# 1-Schematic_USB-C_Serial.net
KiCad netlist of a schematic drawn in EasyEDA
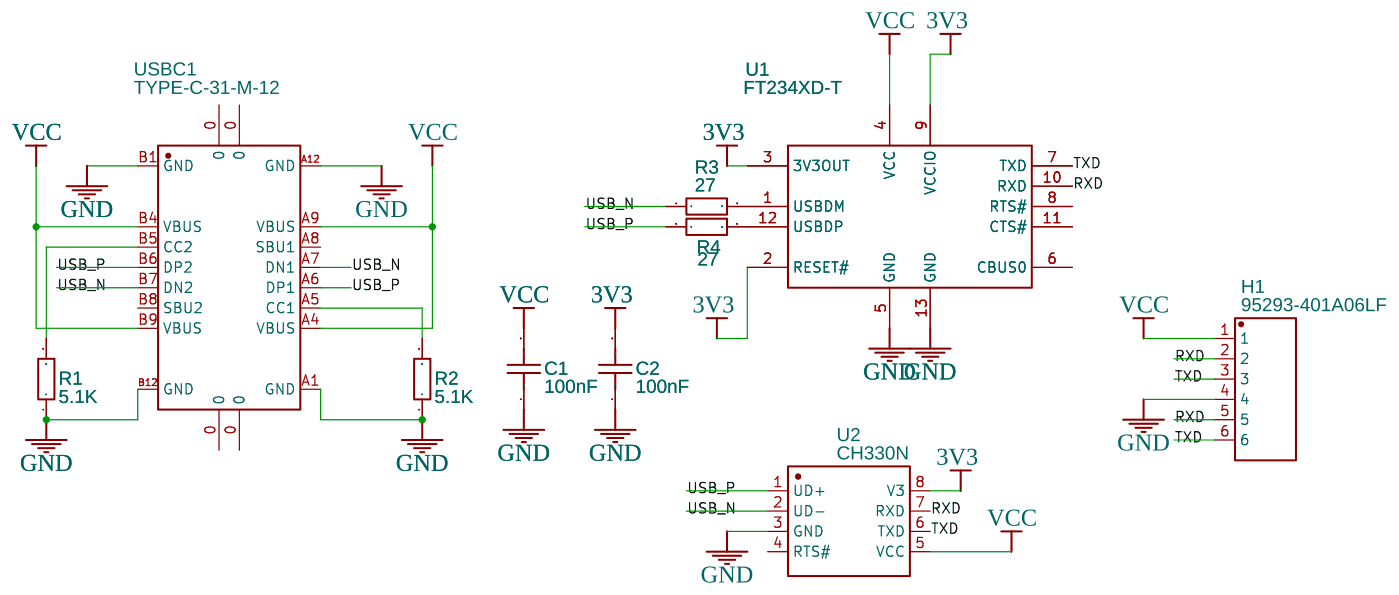
[diagram p0: schematic sheet]

(export (version "E")
  (design (tool "Eeschema 10.0.6"))
  (components
    (comp (ref "C1")
      (value "100nF")
      (fields
        (field (name "BOM_Manufacturer Part") "CC0603KRX7R9BB104")
        (field (name "BOM_Supplier Part") "C14663")
      )
      (libsource (lib "") (part "CC0603KRX7R9BB104"))
    )
    (comp (ref "C2")
      (value "100nF")
      (fields
        (field (name "BOM_Manufacturer Part") "CC0603KRX7R9BB104")
        (field (name "BOM_Supplier Part") "C14663")
      )
      (libsource (lib "") (part "CC0603KRX7R9BB104"))
    )
    (comp (ref "H1")
      (value "95293-401A06LF")
      (fields (field (name "BOM_Supplier Part") "C178297"))
      (libsource (lib "") (part "Unknown_170_95"))
    )
    (comp (ref "R1")
      (value "5.1K")
      (fields
        (field (name "BOM_Manufacturer Part") "TC0325F5101T5E")
        (field (name "BOM_Supplier Part") "C146211")
      )
      (libsource (lib "") (part "TC0325F5101T5E"))
    )
    (comp (ref "R2")
      (value "5.1K")
      (fields
        (field (name "BOM_Manufacturer Part") "TC0325F5101T5E")
        (field (name "BOM_Supplier Part") "C146211")
      )
      (libsource (lib "") (part "TC0325F5101T5E"))
    )
    (comp (ref "R3")
      (value "27")
      (fields
        (field (name "BOM_Manufacturer Part") "0603WAF270JT5E")
        (field (name "BOM_Supplier Part") "C25190")
      )
      (libsource (lib "") (part "0603WAF270JT5E"))
    )
    (comp (ref "R4")
      (value "27")
      (fields
        (field (name "BOM_Manufacturer Part") "0603WAF270JT5E")
        (field (name "BOM_Supplier Part") "C25190")
      )
      (libsource (lib "") (part "0603WAF270JT5E"))
    )
    (comp (ref "U1")
      (value "FT234XD-T")
      (fields (field (name "BOM_Supplier Part") "C89606"))
      (libsource (lib "") (part "Unknown_0_15"))
    )
    (comp (ref "U2")
      (value "CH330N")
      (fields (field (name "BOM_Supplier Part") "C108996"))
      (libsource (lib "") (part "Unknown_-30_160"))
    )
    (comp (ref "USBC1")
      (value "TYPE-C-31-M-12")
      (fields (field (name "BOM_Supplier Part") "C165948"))
      (libsource (lib "") (part "Unknown_-335_40"))
    )
  )
  (nets
    (net (code "1") (name "/RXD") (class "Default")
      (node (ref "H1") (pin "2") (pinfunction "2_2") (pintype "unspecified"))
      (node (ref "H1") (pin "5") (pinfunction "5_5") (pintype "unspecified"))
      (node (ref "U1") (pin "10") (pinfunction "RXD_10") (pintype "unspecified"))
      (node (ref "U2") (pin "7") (pinfunction "RXD_7") (pintype "unspecified"))
    )
    (net (code "2") (name "/TXD") (class "Default")
      (node (ref "H1") (pin "3") (pinfunction "3_3") (pintype "unspecified"))
      (node (ref "H1") (pin "6") (pinfunction "6_6") (pintype "unspecified"))
      (node (ref "U1") (pin "7") (pinfunction "TXD_7") (pintype "unspecified"))
      (node (ref "U2") (pin "6") (pinfunction "TXD_6") (pintype "unspecified"))
    )
    (net (code "3") (name "/USB_N") (class "Default")
      (node (ref "R3") (pin "1") (pinfunction "1_1") (pintype "input"))
      (node (ref "U2") (pin "2") (pinfunction "UD-_2") (pintype "unspecified"))
      (node (ref "USBC1") (pin "A7") (pinfunction "DN1_A7") (pintype "unspecified"))
      (node (ref "USBC1") (pin "B7") (pinfunction "DN2_B7") (pintype "unspecified"))
    )
    (net (code "4") (name "/USB_P") (class "Default")
      (node (ref "R4") (pin "1") (pinfunction "1_1") (pintype "input"))
      (node (ref "U2") (pin "1") (pinfunction "UD+_1") (pintype "unspecified"))
      (node (ref "USBC1") (pin "A6") (pinfunction "DP1_A6") (pintype "unspecified"))
      (node (ref "USBC1") (pin "B6") (pinfunction "DP2_B6") (pintype "unspecified"))
    )
    (net (code "5") (name "3V3") (class "Default")
      (node (ref "C2") (pin "2") (pinfunction "2_2") (pintype "unspecified"))
      (node (ref "U1") (pin "2") (pinfunction "RESET#_2") (pintype "unspecified"))
      (node (ref "U1") (pin "3") (pinfunction "3V3OUT_3") (pintype "unspecified"))
      (node (ref "U1") (pin "9") (pinfunction "VCCIO_9") (pintype "unspecified"))
      (node (ref "U2") (pin "8") (pinfunction "V3_8") (pintype "unspecified"))
    )
    (net (code "6") (name "GND") (class "Default")
      (node (ref "C1") (pin "1") (pinfunction "1_1") (pintype "unspecified"))
      (node (ref "C2") (pin "1") (pinfunction "1_1") (pintype "unspecified"))
      (node (ref "H1") (pin "4") (pinfunction "4_4") (pintype "unspecified"))
      (node (ref "R1") (pin "1") (pinfunction "1_1") (pintype "input"))
      (node (ref "R2") (pin "1") (pinfunction "1_1") (pintype "input"))
      (node (ref "U1") (pin "13") (pinfunction "GND_13") (pintype "unspecified"))
      (node (ref "U1") (pin "5") (pinfunction "GND_5") (pintype "unspecified"))
      (node (ref "U2") (pin "3") (pinfunction "GND_3") (pintype "unspecified"))
      (node (ref "USBC1") (pin "A1") (pinfunction "GND_A1") (pintype "unspecified"))
      (node (ref "USBC1") (pin "A12") (pinfunction "GND_A12") (pintype "unspecified"))
      (node (ref "USBC1") (pin "B1") (pinfunction "GND_B1") (pintype "unspecified"))
      (node (ref "USBC1") (pin "B12") (pinfunction "GND_B12") (pintype "unspecified"))
    )
    (net (code "7") (name "Net-(U1-USBDM)") (class "Default")
      (node (ref "R3") (pin "2") (pinfunction "2_2") (pintype "input"))
      (node (ref "U1") (pin "1") (pinfunction "USBDM_1") (pintype "unspecified"))
    )
    (net (code "8") (name "Net-(U1-USBDP)") (class "Default")
      (node (ref "R4") (pin "2") (pinfunction "2_2") (pintype "input"))
      (node (ref "U1") (pin "12") (pinfunction "USBDP_12") (pintype "unspecified"))
    )
    (net (code "9") (name "Net-(USBC1-CC1)") (class "Default")
      (node (ref "R2") (pin "2") (pinfunction "2_2") (pintype "input"))
      (node (ref "USBC1") (pin "A5") (pinfunction "CC1_A5") (pintype "unspecified"))
    )
    (net (code "10") (name "Net-(USBC1-CC2)") (class "Default")
      (node (ref "R1") (pin "2") (pinfunction "2_2") (pintype "input"))
      (node (ref "USBC1") (pin "B5") (pinfunction "CC2_B5") (pintype "unspecified"))
    )
    (net (code "11") (name "VCC") (class "Default")
      (node (ref "C1") (pin "2") (pinfunction "2_2") (pintype "unspecified"))
      (node (ref "H1") (pin "1") (pinfunction "1_1") (pintype "unspecified"))
      (node (ref "U1") (pin "4") (pinfunction "VCC_4") (pintype "unspecified"))
      (node (ref "U2") (pin "5") (pinfunction "VCC_5") (pintype "unspecified"))
      (node (ref "USBC1") (pin "A4") (pinfunction "VBUS_A4") (pintype "unspecified"))
      (node (ref "USBC1") (pin "A9") (pinfunction "VBUS_A9") (pintype "unspecified"))
      (node (ref "USBC1") (pin "B4") (pinfunction "VBUS_B4") (pintype "unspecified"))
      (node (ref "USBC1") (pin "B9") (pinfunction "VBUS_B9") (pintype "unspecified"))
    )
    (net (code "12") (name "unconnected-(U1-CBUS0-Pad6)") (class "Default")
      (node (ref "U1") (pin "6") (pinfunction "CBUS0_6") (pintype "unspecified"))
    )
    (net (code "13") (name "unconnected-(U1-CTS#-Pad11)") (class "Default")
      (node (ref "U1") (pin "11") (pinfunction "CTS#_11") (pintype "unspecified"))
    )
    (net (code "14") (name "unconnected-(U1-RTS#-Pad8)") (class "Default")
      (node (ref "U1") (pin "8") (pinfunction "RTS#_8") (pintype "unspecified"))
    )
    (net (code "15") (name "unconnected-(U2-RTS#-Pad4)") (class "Default")
      (node (ref "U2") (pin "4") (pinfunction "RTS#_4") (pintype "unspecified"))
    )
    (net (code "16") (name "unconnected-(USBC1-Pad0)") (class "Default")
      (node (ref "USBC1") (pin "0") (pinfunction "0_0") (pintype "unspecified"))
    )
    (net (code "17") (name "unconnected-(USBC1-Pad0)_1") (class "Default")
      (node (ref "USBC1") (pin "0") (pinfunction "0_0") (pintype "unspecified"))
    )
    (net (code "18") (name "unconnected-(USBC1-Pad0)_2") (class "Default")
      (node (ref "USBC1") (pin "0") (pinfunction "0_0") (pintype "unspecified"))
    )
    (net (code "19") (name "unconnected-(USBC1-Pad0)_3") (class "Default")
      (node (ref "USBC1") (pin "0") (pinfunction "0_0") (pintype "unspecified"))
    )
    (net (code "20") (name "unconnected-(USBC1-SBU1-PadA8)") (class "Default")
      (node (ref "USBC1") (pin "A8") (pinfunction "SBU1_A8") (pintype "unspecified"))
    )
    (net (code "21") (name "unconnected-(USBC1-SBU2-PadB8)") (class "Default")
      (node (ref "USBC1") (pin "B8") (pinfunction "SBU2_B8") (pintype "unspecified"))
    )
  )
)
